# IRComms.net
KiCad netlist of a schematic drawn in Altium Designer
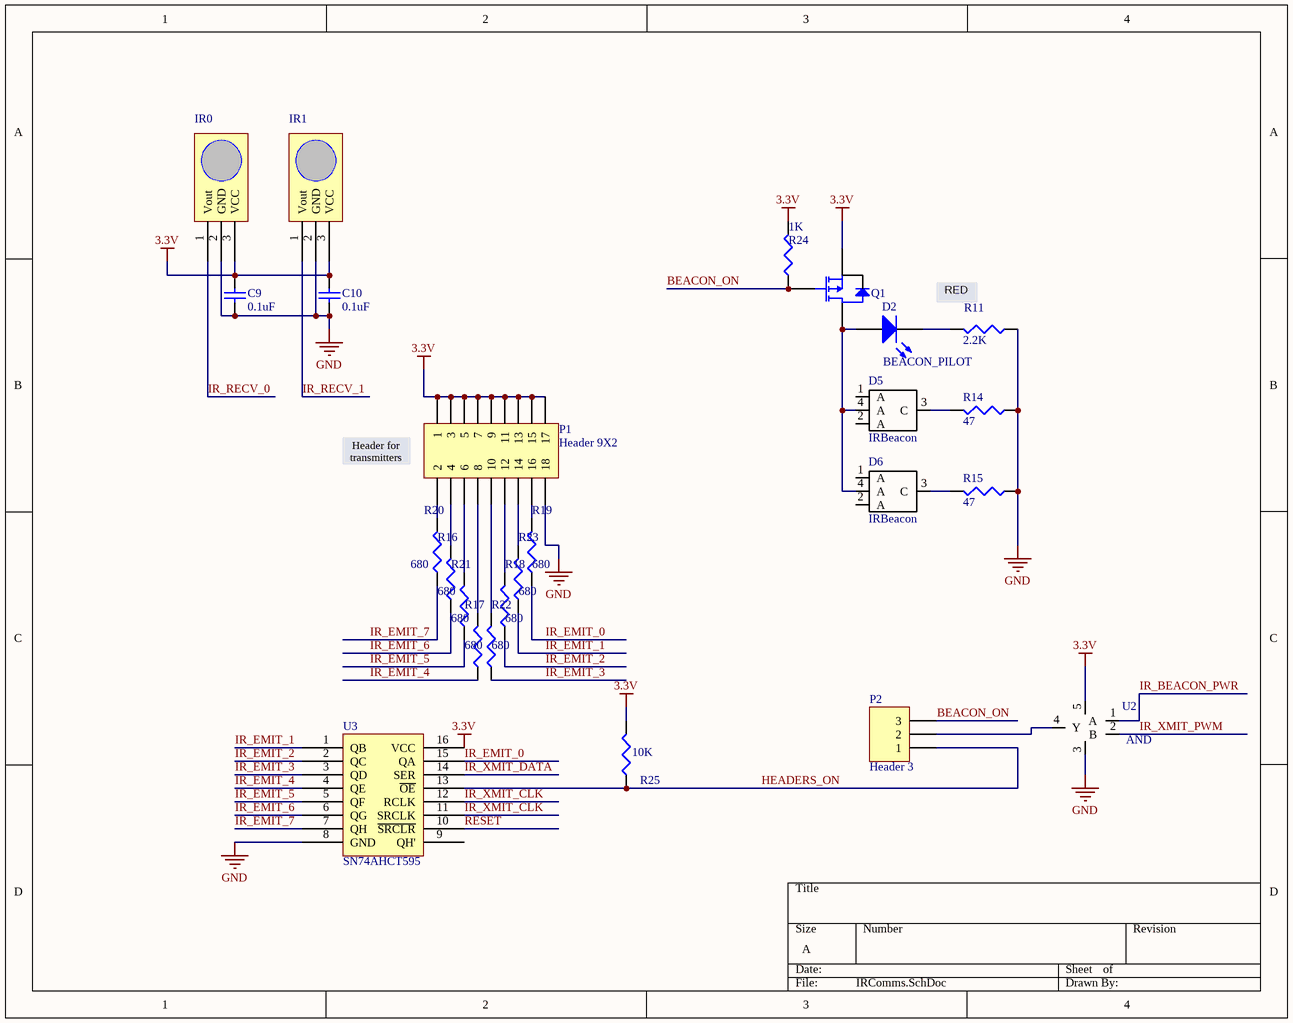
[diagram p0: IRComms.SchDoc]

(export (version "E")
  (design (tool "Eeschema 10.0.6"))
  (components
    (comp (ref "C9")
      (value "0.1uF")
      (footprint "0402")
      (description "Capacitor (Semiconductor SIM Model)")
      (fields (field (name "Comment") "Cap Semi") (field (name "PUBLISHER") "Altium Limited"))
      (libsource (lib "Miscellaneous Devices") (part "Cap Semi"))
    )
    (comp (ref "C10")
      (value "0.1uF")
      (footprint "0402")
      (description "Capacitor (Semiconductor SIM Model)")
      (fields (field (name "Comment") "Cap Semi") (field (name "PUBLISHER") "Altium Limited"))
      (libsource (lib "Miscellaneous Devices") (part "Cap Semi"))
    )
    (comp (ref "D2")
      (value "BEACON_PILOT")
      (footprint "SurfaceMount(603)")
      (libsource (lib "mrone") (part "LED"))
    )
    (comp (ref "D5") (value "IRBeacon") (footprint "IRBeacon") (libsource (lib "mrone") (part "IRBeacon")))
    (comp (ref "D6") (value "IRBeacon") (footprint "IRBeacon") (libsource (lib "mrone") (part "IRBeacon")))
    (comp (ref "IR0")
      (value "GP1UX31QS")
      (footprint "GP1UX31QS")
      (libsource (lib "mrone") (part "GP1UX31QS"))
    )
    (comp (ref "IR1")
      (value "GP1UX31QS")
      (footprint "GP1UX31QS")
      (libsource (lib "mrone") (part "GP1UX31QS"))
    )
    (comp (ref "P1")
      (value "Header 9X2")
      (footprint "HDR2X9")
      (description "Header, 9-Pin, Dual row")
      (fields (field (name "PUBLISHER") "Altium Limited"))
      (libsource (lib "Miscellaneous Connectors") (part "Header 9X2"))
    )
    (comp (ref "P2")
      (value "Header 3")
      (footprint "HDR1X3")
      (description "Header, 3-Pin")
      (fields (field (name "PUBLISHER") "Altium Limited"))
      (libsource (lib "Miscellaneous Connectors") (part "Header 3"))
    )
    (comp (ref "Q1") (value "P-Mosfet") (footprint "SOT-23") (libsource (lib "mrone") (part "P-Mosfet")))
    (comp (ref "R11")
      (value "2.2K")
      (footprint "J1-0603")
      (description "Resistor")
      (fields (field (name "Comment") "Res3") (field (name "PUBLISHER") "Altium Limited"))
      (libsource (lib "Miscellaneous Devices") (part "Res3"))
    )
    (comp (ref "R14")
      (value "47")
      (footprint "J1-0603")
      (description "Resistor")
      (fields (field (name "Comment") "Res3") (field (name "PUBLISHER") "Altium Limited"))
      (libsource (lib "Miscellaneous Devices") (part "Res3"))
    )
    (comp (ref "R15")
      (value "47")
      (footprint "J1-0603")
      (description "Resistor")
      (fields (field (name "Comment") "Res3") (field (name "PUBLISHER") "Altium Limited"))
      (libsource (lib "Miscellaneous Devices") (part "Res3"))
    )
    (comp (ref "R16")
      (value "680")
      (footprint "J1-0603")
      (description "Resistor")
      (fields (field (name "Comment") "Res3") (field (name "PUBLISHER") "Altium Limited"))
      (libsource (lib "Miscellaneous Devices") (part "Res3"))
    )
    (comp (ref "R17")
      (value "680")
      (footprint "J1-0603")
      (description "Resistor")
      (fields (field (name "Comment") "Res3") (field (name "PUBLISHER") "Altium Limited"))
      (libsource (lib "Miscellaneous Devices") (part "Res3"))
    )
    (comp (ref "R18")
      (value "680")
      (footprint "J1-0603")
      (description "Resistor")
      (fields (field (name "Comment") "Res3") (field (name "PUBLISHER") "Altium Limited"))
      (libsource (lib "Miscellaneous Devices") (part "Res3"))
    )
    (comp (ref "R19")
      (value "680")
      (footprint "J1-0603")
      (description "Resistor")
      (fields (field (name "Comment") "Res3") (field (name "PUBLISHER") "Altium Limited"))
      (libsource (lib "Miscellaneous Devices") (part "Res3"))
    )
    (comp (ref "R20")
      (value "680")
      (footprint "J1-0603")
      (description "Resistor")
      (fields (field (name "Comment") "Res3") (field (name "PUBLISHER") "Altium Limited"))
      (libsource (lib "Miscellaneous Devices") (part "Res3"))
    )
    (comp (ref "R21")
      (value "680")
      (footprint "J1-0603")
      (description "Resistor")
      (fields (field (name "Comment") "Res3") (field (name "PUBLISHER") "Altium Limited"))
      (libsource (lib "Miscellaneous Devices") (part "Res3"))
    )
    (comp (ref "R22")
      (value "680")
      (footprint "J1-0603")
      (description "Resistor")
      (fields (field (name "Comment") "Res3") (field (name "PUBLISHER") "Altium Limited"))
      (libsource (lib "Miscellaneous Devices") (part "Res3"))
    )
    (comp (ref "R23")
      (value "680")
      (footprint "J1-0603")
      (description "Resistor")
      (fields (field (name "Comment") "Res3") (field (name "PUBLISHER") "Altium Limited"))
      (libsource (lib "Miscellaneous Devices") (part "Res3"))
    )
    (comp (ref "R24")
      (value "1K")
      (footprint "J1-0603")
      (description "Resistor")
      (fields (field (name "Comment") "Res3") (field (name "PUBLISHER") "Altium Limited"))
      (libsource (lib "Miscellaneous Devices") (part "Res3"))
    )
    (comp (ref "R25")
      (value "10K")
      (footprint "J1-0603")
      (description "Resistor")
      (fields (field (name "Comment") "Res3") (field (name "PUBLISHER") "Altium Limited"))
      (libsource (lib "Miscellaneous Devices") (part "Res3"))
    )
    (comp (ref "U2")
      (value "AND")
      (footprint "SOT-23-5")
      (description "2 input AND gate")
      (libsource (lib "mrone") (part "AND_gate"))
    )
    (comp (ref "U3")
      (value "SN74AHCT595")
      (footprint "TSSOP-16")
      (description "shift register")
      (libsource (lib "mrone") (part "SN74AHCT595"))
    )
  )
  (nets
    (net (code "1") (name "/BEACON_ON") (class "Default")
      (node (ref "P2") (pin "3") (pinfunction "3_3") (pintype "passive"))
      (node (ref "Q1") (pin "1") (pinfunction "G_1") (pintype "passive"))
      (node (ref "R24") (pin "1") (pinfunction "1_1") (pintype "passive"))
    )
    (net (code "2") (name "/HEADERS_ON") (class "Default")
      (node (ref "P2") (pin "1") (pinfunction "1_1") (pintype "passive"))
      (node (ref "R25") (pin "1") (pinfunction "1_1") (pintype "passive"))
      (node (ref "U3") (pin "13") (pinfunction "~{OE}_13") (pintype "passive"))
    )
    (net (code "3") (name "/IR_BEACON_PWR") (class "Default")
      (node (ref "U2") (pin "1") (pinfunction "A_1") (pintype "passive"))
    )
    (net (code "4") (name "/IR_EMIT_0") (class "Default")
      (node (ref "R19") (pin "1") (pinfunction "1_1") (pintype "passive"))
      (node (ref "U3") (pin "15") (pinfunction "QA_15") (pintype "passive"))
    )
    (net (code "5") (name "/IR_EMIT_1") (class "Default")
      (node (ref "R23") (pin "1") (pinfunction "1_1") (pintype "passive"))
      (node (ref "U3") (pin "1") (pinfunction "QB_1") (pintype "passive"))
    )
    (net (code "6") (name "/IR_EMIT_2") (class "Default")
      (node (ref "R18") (pin "1") (pinfunction "1_1") (pintype "passive"))
      (node (ref "U3") (pin "2") (pinfunction "QC_2") (pintype "passive"))
    )
    (net (code "7") (name "/IR_EMIT_3") (class "Default")
      (node (ref "R22") (pin "1") (pinfunction "1_1") (pintype "passive"))
      (node (ref "U3") (pin "3") (pinfunction "QD_3") (pintype "passive"))
    )
    (net (code "8") (name "/IR_EMIT_4") (class "Default")
      (node (ref "R17") (pin "1") (pinfunction "1_1") (pintype "passive"))
      (node (ref "U3") (pin "4") (pinfunction "QE_4") (pintype "passive"))
    )
    (net (code "9") (name "/IR_EMIT_5") (class "Default")
      (node (ref "R21") (pin "1") (pinfunction "1_1") (pintype "passive"))
      (node (ref "U3") (pin "5") (pinfunction "QF_5") (pintype "passive"))
    )
    (net (code "10") (name "/IR_EMIT_6") (class "Default")
      (node (ref "R16") (pin "1") (pinfunction "1_1") (pintype "passive"))
      (node (ref "U3") (pin "6") (pinfunction "QG_6") (pintype "passive"))
    )
    (net (code "11") (name "/IR_EMIT_7") (class "Default")
      (node (ref "R20") (pin "1") (pinfunction "1_1") (pintype "passive"))
      (node (ref "U3") (pin "7") (pinfunction "QH_7") (pintype "passive"))
    )
    (net (code "12") (name "/IR_RECV_0") (class "Default")
      (node (ref "IR0") (pin "1") (pinfunction "Vout_1") (pintype "passive"))
    )
    (net (code "13") (name "/IR_RECV_1") (class "Default")
      (node (ref "IR1") (pin "1") (pinfunction "Vout_1") (pintype "passive"))
    )
    (net (code "14") (name "/IR_XMIT_CLK") (class "Default")
      (node (ref "U3") (pin "11") (pinfunction "SRCLK_11") (pintype "passive"))
      (node (ref "U3") (pin "12") (pinfunction "RCLK_12") (pintype "passive"))
    )
    (net (code "15") (name "/IR_XMIT_DATA") (class "Default")
      (node (ref "U3") (pin "14") (pinfunction "SER_14") (pintype "passive"))
    )
    (net (code "16") (name "/IR_XMIT_PWM") (class "Default")
      (node (ref "U2") (pin "2") (pinfunction "B_2") (pintype "passive"))
    )
    (net (code "17") (name "/RESET") (class "Default")
      (node (ref "U3") (pin "10") (pinfunction "~{SRCLR}_10") (pintype "passive"))
    )
    (net (code "18") (name "3.3V") (class "Default")
      (node (ref "C10") (pin "2") (pinfunction "2_2") (pintype "passive"))
      (node (ref "C9") (pin "2") (pinfunction "2_2") (pintype "passive"))
      (node (ref "IR0") (pin "3") (pinfunction "VCC_3") (pintype "power_in"))
      (node (ref "IR1") (pin "3") (pinfunction "VCC_3") (pintype "power_in"))
      (node (ref "P1") (pin "1") (pinfunction "1_1") (pintype "passive"))
      (node (ref "P1") (pin "11") (pinfunction "11_11") (pintype "passive"))
      (node (ref "P1") (pin "13") (pinfunction "13_13") (pintype "passive"))
      (node (ref "P1") (pin "15") (pinfunction "15_15") (pintype "passive"))
      (node (ref "P1") (pin "17") (pinfunction "17_17") (pintype "passive"))
      (node (ref "P1") (pin "3") (pinfunction "3_3") (pintype "passive"))
      (node (ref "P1") (pin "5") (pinfunction "5_5") (pintype "passive"))
      (node (ref "P1") (pin "7") (pinfunction "7_7") (pintype "passive"))
      (node (ref "P1") (pin "9") (pinfunction "9_9") (pintype "passive"))
      (node (ref "Q1") (pin "2") (pinfunction "S_2") (pintype "passive"))
      (node (ref "R24") (pin "2") (pinfunction "2_2") (pintype "passive"))
      (node (ref "R25") (pin "2") (pinfunction "2_2") (pintype "passive"))
      (node (ref "U2") (pin "5") (pinfunction "VCC_5") (pintype "passive"))
      (node (ref "U3") (pin "16") (pinfunction "VCC_16") (pintype "passive"))
    )
    (net (code "19") (name "GND") (class "Default")
      (node (ref "C10") (pin "1") (pinfunction "1_1") (pintype "passive"))
      (node (ref "C9") (pin "1") (pinfunction "1_1") (pintype "passive"))
      (node (ref "IR0") (pin "2") (pinfunction "GND_2") (pintype "power_in"))
      (node (ref "IR1") (pin "2") (pinfunction "GND_2") (pintype "power_in"))
      (node (ref "P1") (pin "18") (pinfunction "18_18") (pintype "passive"))
      (node (ref "R11") (pin "1") (pinfunction "1_1") (pintype "passive"))
      (node (ref "R14") (pin "1") (pinfunction "1_1") (pintype "passive"))
      (node (ref "R15") (pin "1") (pinfunction "1_1") (pintype "passive"))
      (node (ref "U2") (pin "3") (pinfunction "GND_3") (pintype "passive"))
      (node (ref "U3") (pin "8") (pinfunction "GND_8") (pintype "passive"))
    )
    (net (code "20") (name "Net-(D2-A)") (class "Default")
      (node (ref "D2") (pin "1") (pinfunction "A_1") (pintype "passive"))
      (node (ref "D5") (pin "4") (pinfunction "A_4") (pintype "passive"))
      (node (ref "D6") (pin "4") (pinfunction "A_4") (pintype "passive"))
      (node (ref "Q1") (pin "3") (pinfunction "D_3") (pintype "passive"))
    )
    (net (code "21") (name "Net-(D2-K)") (class "Default")
      (node (ref "D2") (pin "2") (pinfunction "K_2") (pintype "passive"))
      (node (ref "R11") (pin "2") (pinfunction "2_2") (pintype "passive"))
    )
    (net (code "22") (name "Net-(D5-C)") (class "Default")
      (node (ref "D5") (pin "3") (pinfunction "C_3") (pintype "passive"))
      (node (ref "R14") (pin "2") (pinfunction "2_2") (pintype "passive"))
    )
    (net (code "23") (name "Net-(D6-C)") (class "Default")
      (node (ref "D6") (pin "3") (pinfunction "C_3") (pintype "passive"))
      (node (ref "R15") (pin "2") (pinfunction "2_2") (pintype "passive"))
    )
    (net (code "24") (name "Net-(P1-Pad2)") (class "Default")
      (node (ref "P1") (pin "2") (pinfunction "2_2") (pintype "passive"))
      (node (ref "R20") (pin "2") (pinfunction "2_2") (pintype "passive"))
    )
    (net (code "25") (name "Net-(P1-Pad4)") (class "Default")
      (node (ref "P1") (pin "4") (pinfunction "4_4") (pintype "passive"))
      (node (ref "R16") (pin "2") (pinfunction "2_2") (pintype "passive"))
    )
    (net (code "26") (name "Net-(P1-Pad6)") (class "Default")
      (node (ref "P1") (pin "6") (pinfunction "6_6") (pintype "passive"))
      (node (ref "R21") (pin "2") (pinfunction "2_2") (pintype "passive"))
    )
    (net (code "27") (name "Net-(P1-Pad8)") (class "Default")
      (node (ref "P1") (pin "8") (pinfunction "8_8") (pintype "passive"))
      (node (ref "R17") (pin "2") (pinfunction "2_2") (pintype "passive"))
    )
    (net (code "28") (name "Net-(P1-Pad10)") (class "Default")
      (node (ref "P1") (pin "10") (pinfunction "10_10") (pintype "passive"))
      (node (ref "R22") (pin "2") (pinfunction "2_2") (pintype "passive"))
    )
    (net (code "29") (name "Net-(P1-Pad12)") (class "Default")
      (node (ref "P1") (pin "12") (pinfunction "12_12") (pintype "passive"))
      (node (ref "R18") (pin "2") (pinfunction "2_2") (pintype "passive"))
    )
    (net (code "30") (name "Net-(P1-Pad14)") (class "Default")
      (node (ref "P1") (pin "14") (pinfunction "14_14") (pintype "passive"))
      (node (ref "R23") (pin "2") (pinfunction "2_2") (pintype "passive"))
    )
    (net (code "31") (name "Net-(P1-Pad16)") (class "Default")
      (node (ref "P1") (pin "16") (pinfunction "16_16") (pintype "passive"))
      (node (ref "R19") (pin "2") (pinfunction "2_2") (pintype "passive"))
    )
    (net (code "32") (name "Net-(U2-Y)") (class "Default")
      (node (ref "P2") (pin "2") (pinfunction "2_2") (pintype "passive"))
      (node (ref "U2") (pin "4") (pinfunction "Y_4") (pintype "passive"))
    )
    (net (code "33") (name "unconnected-(D5-A-Pad1)") (class "Default")
      (node (ref "D5") (pin "1") (pinfunction "A_1") (pintype "passive"))
    )
    (net (code "34") (name "unconnected-(D5-A-Pad2)") (class "Default")
      (node (ref "D5") (pin "2") (pinfunction "A_2") (pintype "passive"))
    )
    (net (code "35") (name "unconnected-(D6-A-Pad1)") (class "Default")
      (node (ref "D6") (pin "1") (pinfunction "A_1") (pintype "passive"))
    )
    (net (code "36") (name "unconnected-(D6-A-Pad2)") (class "Default")
      (node (ref "D6") (pin "2") (pinfunction "A_2") (pintype "passive"))
    )
    (net (code "37") (name "unconnected-(U3-QH'-Pad9)") (class "Default")
      (node (ref "U3") (pin "9") (pinfunction "QH'_9") (pintype "passive"))
    )
  )
)
